# 7V_Buck_For_LDOs.net
KiCad netlist of a schematic drawn in Altium Designer
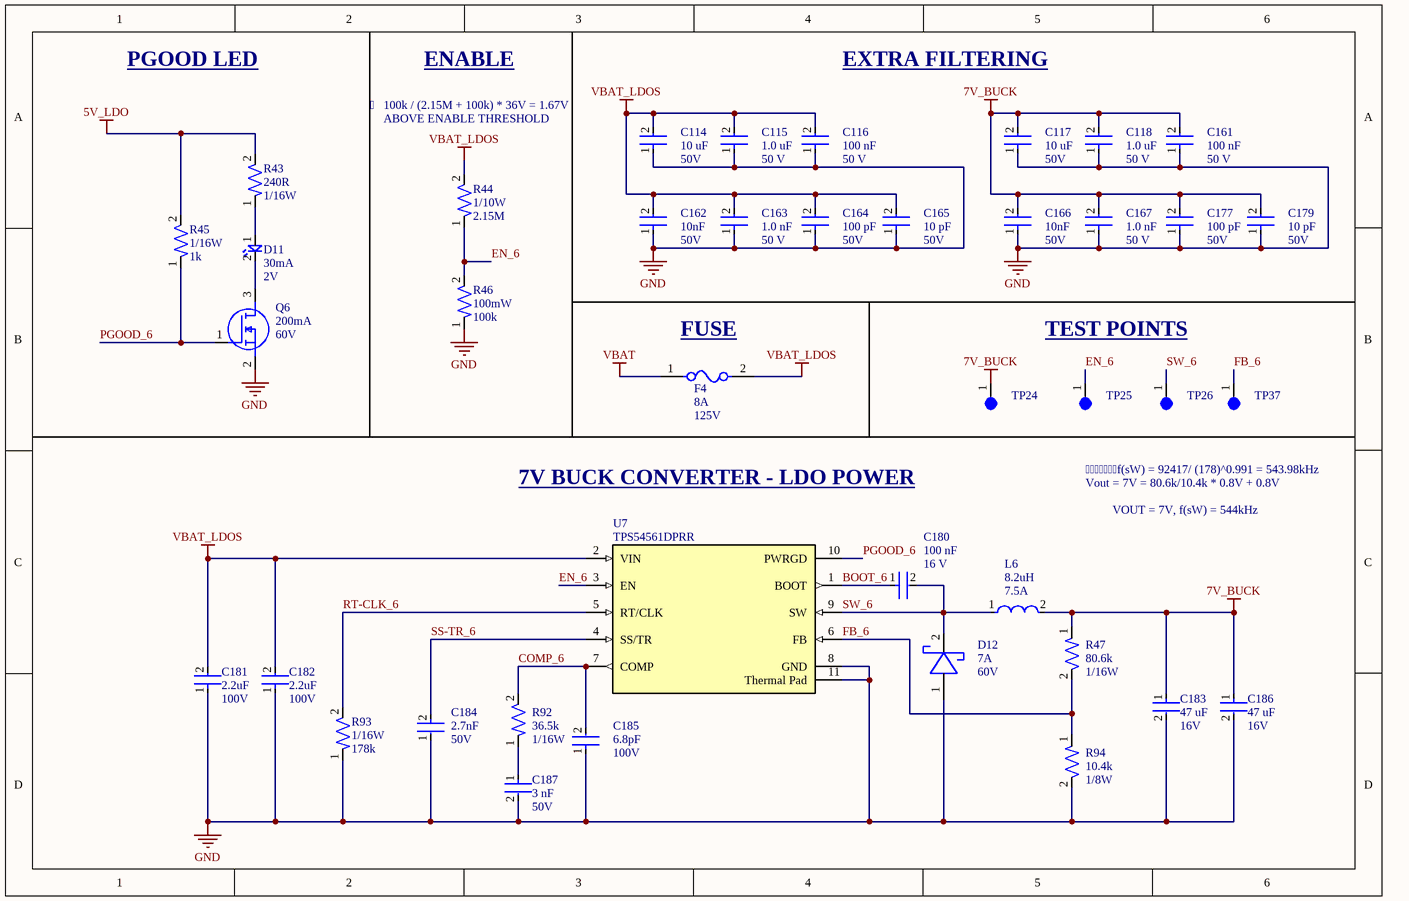
[diagram p0: 7V_Buck_For_LDOs.SchDoc]

(export (version "E")
  (design (tool "Eeschema 10.0.6"))
  (components
    (comp (ref "C114")
      (value "CL32B106KBJNNNE")
      (footprint "CAP-1210")
      (description "CAP CER 10UF 50V X7R 1210")
      (fields (field (name "VOLTAGE") "50V") (field (name "CAPACITANCE") "10 uF"))
      (libsource (lib "JLC_25") (part "CAP-10U-0002"))
    )
    (comp (ref "C115")
      (value "CC0805KKX7R9BB105")
      (footprint "CAP-0805")
      (description "CAP CER 1UF 50V X7R 0805")
      (fields (field (name "VOLTAGE") "50 V") (field (name "CAPACITANCE") "1.0 uF"))
      (libsource (lib "JLC_25") (part "CAP-1U-0001"))
    )
    (comp (ref "C116")
      (value "CC0805KRX7R9BB104")
      (footprint "CAP-0805")
      (description "CAP CER 0.1UF 50V X7R 0805")
      (fields (field (name "VOLTAGE RATING") "50 V") (field (name "CAPACITANCE") "100 nF"))
      (libsource (lib "JLC_25") (part "CAP-0.1U-0002"))
    )
    (comp (ref "C117")
      (value "CL32B106KBJNNNE")
      (footprint "CAP-1210")
      (description "CAP CER 10UF 50V X7R 1210")
      (fields (field (name "VOLTAGE") "50V") (field (name "CAPACITANCE") "10 uF"))
      (libsource (lib "JLC_25") (part "CAP-10U-0002"))
    )
    (comp (ref "C118")
      (value "CC0805KKX7R9BB105")
      (footprint "CAP-0805")
      (description "CAP CER 1UF 50V X7R 0805")
      (fields (field (name "VOLTAGE") "50 V") (field (name "CAPACITANCE") "1.0 uF"))
      (libsource (lib "JLC_25") (part "CAP-1U-0001"))
    )
    (comp (ref "C161")
      (value "CC0805KRX7R9BB104")
      (footprint "CAP-0805")
      (description "CAP CER 0.1UF 50V X7R 0805")
      (fields (field (name "VOLTAGE RATING") "50 V") (field (name "CAPACITANCE") "100 nF"))
      (libsource (lib "JLC_25") (part "CAP-0.1U-0002"))
    )
    (comp (ref "C162")
      (value "GRM2195C1H103JA01D")
      (footprint "CAP-0805")
      (description "CAP CER 10000PF 50V C0G/NP0 0805")
      (fields (field (name "VOLTAGE") "50V") (field (name "CAPACITANCE") "10nF"))
      (libsource (lib "JLC_25") (part "CAP-10N-0001"))
    )
    (comp (ref "C163")
      (value "CC0402KRX7R9BB102")
      (footprint "CAP-0402")
      (description "CAP CER 1000PF 50V X7R 0402")
      (fields (field (name "VOLTAGE") "50 V") (field (name "CAPACITANCE") "1.0 nF"))
      (libsource (lib "JLC_25") (part "CAP-1N-0001"))
    )
    (comp (ref "C164")
      (value "CC0402JRNPO9BN101")
      (footprint "CAP-0402")
      (description "CAP CER 100PF 50V C0G/NPO 0402")
      (fields (field (name "CAPACITANCE") "100 pF") (field (name "VOLTAGE") "50V"))
      (libsource (lib "JLC_25") (part "CAP-100P-0001"))
    )
    (comp (ref "C165")
      (value "CC0402JRNPO9BN100")
      (footprint "CAP-0402")
      (description "CAP CER 10PF 50V C0G/NPO 0402")
      (fields (field (name "CAPACITANCE") "10 pF") (field (name "VOLTAGE") "50V"))
      (libsource (lib "JLC_25") (part "CAP-10P-0001"))
    )
    (comp (ref "C166")
      (value "GRM2195C1H103JA01D")
      (footprint "CAP-0805")
      (description "CAP CER 10000PF 50V C0G/NP0 0805")
      (fields (field (name "VOLTAGE") "50V") (field (name "CAPACITANCE") "10nF"))
      (libsource (lib "JLC_25") (part "CAP-10N-0001"))
    )
    (comp (ref "C167")
      (value "CC0402KRX7R9BB102")
      (footprint "CAP-0402")
      (description "CAP CER 1000PF 50V X7R 0402")
      (fields (field (name "VOLTAGE") "50 V") (field (name "CAPACITANCE") "1.0 nF"))
      (libsource (lib "JLC_25") (part "CAP-1N-0001"))
    )
    (comp (ref "C177")
      (value "CC0402JRNPO9BN101")
      (footprint "CAP-0402")
      (description "CAP CER 100PF 50V C0G/NPO 0402")
      (fields (field (name "CAPACITANCE") "100 pF") (field (name "VOLTAGE") "50V"))
      (libsource (lib "JLC_25") (part "CAP-100P-0001"))
    )
    (comp (ref "C179")
      (value "CC0402JRNPO9BN100")
      (footprint "CAP-0402")
      (description "CAP CER 10PF 50V C0G/NPO 0402")
      (fields (field (name "CAPACITANCE") "10 pF") (field (name "VOLTAGE") "50V"))
      (libsource (lib "JLC_25") (part "CAP-10P-0001"))
    )
    (comp (ref "C180")
      (value "CC0402KRX7R7BB104")
      (footprint "CAP-0402")
      (description "CAP CER 0.1UF 16V X7R 0402")
      (fields (field (name "VOLTAGE RATING") "16 V") (field (name "CAPACITANCE") "100 nF"))
      (libsource (lib "JLC_25") (part "CAP-0.1U-0001"))
    )
    (comp (ref "C181")
      (value "CC1206KKX7R0BB225")
      (footprint "CAP-1206")
      (description "CAP CER 2.2UF 100V X7R 1206")
      (fields (field (name "CAPACITANCE") "2.2uF") (field (name "VOLTAGE") "100V"))
      (libsource (lib "JLC_25") (part "CAP-2.2U-0001"))
    )
    (comp (ref "C182")
      (value "CC1206KKX7R0BB225")
      (footprint "CAP-1206")
      (description "CAP CER 2.2UF 100V X7R 1206")
      (fields (field (name "CAPACITANCE") "2.2uF") (field (name "VOLTAGE") "100V"))
      (libsource (lib "JLC_25") (part "CAP-2.2U-0001"))
    )
    (comp (ref "C183")
      (value "GRM32ER61C476KE15L")
      (footprint "CAP-1210")
      (description "CAP CER 47UF 16V X5R 1210")
      (fields (field (name "CAPACITANCE") "47 uF") (field (name "VOLTAGE") "16V"))
      (libsource (lib "JLC_25") (part "CAP-47U-0002"))
    )
    (comp (ref "C184")
      (value "GRM2165C1H272JA01D")
      (footprint "CAP-0805")
      (description "CAP CER 2700PF 50V C0G/NP0 0805")
      (fields (field (name "VOLTAGE") "50V") (field (name "CAPACITANCE") "2.7nF"))
      (libsource (lib "JLC_25") (part "CAP-2.7N-0001"))
    )
    (comp (ref "C185")
      (value "CC0603CRNPO0BN6R8")
      (footprint "CAP-0603")
      (description "CAP CER 6.8PF 100V C0G/NPO 0603")
      (fields (field (name "VOLTAGE") "100V") (field (name "CAPACITANCE") "6.8pF"))
      (libsource (lib "JLC_25") (part "CAP-6.8P-0001"))
    )
    (comp (ref "C186")
      (value "GRM32ER61C476KE15L")
      (footprint "CAP-1210")
      (description "CAP CER 47UF 16V X5R 1210")
      (fields (field (name "CAPACITANCE") "47 uF") (field (name "VOLTAGE") "16V"))
      (libsource (lib "JLC_25") (part "CAP-47U-0002"))
    )
    (comp (ref "C187")
      (value "GRM1885C1H302JA01D")
      (footprint "CAP-0603")
      (description "3000 pF ±5% 50V Ceramic Capacitor C0G, NP0 0603 (1608 Metric)")
      (fields (field (name "VOLTAGE") "50V") (field (name "CAPACITANCE") "3 nF"))
      (libsource (lib "JLC_25") (part "CAP-3N-0001"))
    )
    (comp (ref "D11")
      (value "BL-HKC36G-AV-TRB")
      (footprint "LED-0603")
      (description "LED YELLOW CLEAR 0603 SMD")
      (fields (field (name "FORWARD CURRENT") "30mA") (field (name "FORWARD VOLTAGE") "2V"))
      (libsource (lib "JLC_25") (part "LED-0001"))
    )
    (comp (ref "D12")
      (value "PDS760-13")
      (footprint "DO-POWERDI5")
      (description "DIODE SCHOTTKY 60V 7A POWERDI5")
      (fields (field (name "FORWARD CURRENT") "7A") (field (name "REVERSE VOLTAGE (DC)") "60V"))
      (libsource (lib "JLC_25") (part "DIO-SCHOTTKY-0001"))
    )
    (comp (ref "F4")
      (value "01550900M")
      (footprint "FUSE-0001")
      (description "FUSE BLOK CARTRIDGE 125V 10A SMD")
      (fields (field (name "FUSE CURRENT") "8A") (field (name "VOLTAGE RATING") "125V"))
      (libsource (lib "JLC_25") (part "FUSE-0001"))
    )
    (comp (ref "L6")
      (value "IHLP2525CZER8R2M01")
      (footprint "IND25X25CZ")
      (description "8.2 µH Shielded Molded Inductor 4 A 68mOhm Max Nonstandard")
      (fields (field (name "INDUCTANCE") "8.2uH") (field (name "CURRENT RATING") "7.5A"))
      (libsource (lib "JLC_25") (part "IND-8.2U-0001"))
    )
    (comp (ref "Q6")
      (value "T2N7002AK,LM")
      (footprint "IC-SOT23-3")
      (description "MOSFET N-CH 60V 200MA SOT23")
      (fields (field (name "CONTINUOUS CURRENT") "200mA") (field (name "VOLTAGE") "60V"))
      (libsource (lib "JLC_25") (part "NMOS-200MA-0001"))
    )
    (comp (ref "R43")
      (value "RC0402FR-07240RL")
      (footprint "RES-0402")
      (description "240R 0.063W 1% 0402 (1005 Metric)  SMD")
      (fields
        (field (name "TOLERANCE") "1%")
        (field (name "RESISTANCE") "240R")
        (field (name "POWER") "1/16W")
      )
      (libsource (lib "JLC_25") (part "RES-240-0001"))
    )
    (comp (ref "R44")
      (value "RC0603FR-072M15L")
      (footprint "RES-0603")
      (description "RES SMD 2.15M OHM 1% 1/10W 0603")
      (fields
        (field (name "TOLERANCE") "1%")
        (field (name "POWER") "1/10W")
        (field (name "RESISTANCE") "2.15M")
      )
      (libsource (lib "JLC_25") (part "RES-2.15M-0001"))
    )
    (comp (ref "R45")
      (value "RC0402FR-071KL")
      (footprint "RES-0402")
      (description "RES 1K OHM 1% 1/16W 0402")
      (fields (field (name "TOLERANCE") "1%") (field (name "POWER") "1/16W") (field (name "RESISTANCE") "1k"))
      (libsource (lib "JLC_25") (part "RES-1k-0001"))
    )
    (comp (ref "R46")
      (value "RC0603FR-07100KL")
      (footprint "RES-0603")
      (description "RES SMD 100K OHM 1% 1/10W 0603")
      (fields
        (field (name "TOLERANCE") "1%")
        (field (name "POWER") "100mW")
        (field (name "RESISTANCE") "100k")
      )
      (libsource (lib "JLC_25") (part "RES-100k-0001"))
    )
    (comp (ref "R47")
      (value "RC0402FR-0780K6L")
      (footprint "RES-0402")
      (description "80.6 kOhms ±1% 0.063W, 1/16W Chip Resistor 0402 (1005 Metric) Moisture Resistant Thick Film")
      (fields
        (field (name "TOLERANCE") "1%")
        (field (name "RESISTANCE") "80.6k")
        (field (name "POWER") "1/16W")
      )
      (libsource (lib "JLC_25") (part "RES-80.6k-0001"))
    )
    (comp (ref "R92")
      (value "RC0402FR-0736K5L")
      (footprint "RES-0402")
      (description "36.5 kOhms ±1% 0.063W, 1/16W Chip Resistor 0402 (1005 Metric) Moisture Resistant Thick Film")
      (fields (field (name "POWER") "1/16W") (field (name "RESISTANCE") "36.5k"))
      (libsource (lib "JLC_25") (part "RES-36.5k-0001"))
    )
    (comp (ref "R93")
      (value "RTT021783FTH")
      (footprint "RES-0402")
      (description "62.5mW Thick Film Resistors 50V ±100ppm/℃ ±1% 178kΩ 0402 Chip Resistor - Surface Mount ROHS")
      (fields
        (field (name "TOLERANCE") "1%")
        (field (name "POWER") "1/16W")
        (field (name "RESISTANCE") "178k")
      )
      (libsource (lib "JLC_25") (part "RES-178k-0001_1"))
    )
    (comp (ref "R94")
      (value "RT0805BRD0710K4L")
      (footprint "RES-0805")
      (description "10.4 kOhms ±0.1% 0.125W, 1/8W Chip Resistor 0805 (2012 Metric) Thin Film")
      (fields
        (field (name "TOLERANCE") "1%")
        (field (name "POWER") "1/8W")
        (field (name "RESISTANCE") "10.4k")
      )
      (libsource (lib "JLC_25") (part "RES-10.4k-0001"))
    )
    (comp (ref "TP24")
      (value "5003")
      (footprint "TEST-POINT-0001")
      (description "Oranange PC Test Point, Miniature Phoisphor Bronze Silver Plating Through Hole Mounting Type")
      (libsource (lib "*") (part "TEST-POINT-0001"))
    )
    (comp (ref "TP25")
      (value "5003")
      (footprint "TEST-POINT-0001")
      (description "Oranange PC Test Point, Miniature Phoisphor Bronze Silver Plating Through Hole Mounting Type")
      (libsource (lib "*") (part "TEST-POINT-0001"))
    )
    (comp (ref "TP26")
      (value "5003")
      (footprint "TEST-POINT-0001")
      (description "Oranange PC Test Point, Miniature Phoisphor Bronze Silver Plating Through Hole Mounting Type")
      (libsource (lib "*") (part "TEST-POINT-0001"))
    )
    (comp (ref "TP37")
      (value "5003")
      (footprint "TEST-POINT-0001")
      (description "Oranange PC Test Point, Miniature Phoisphor Bronze Silver Plating Through Hole Mounting Type")
      (libsource (lib "*") (part "TEST-POINT-0001"))
    )
    (comp (ref "U7")
      (value "TPS54561DPRR")
      (footprint "IC-10WSON")
      (description "IC REG BUCK ADJ 5A 10WSON")
      (libsource (lib "JLC_25") (part "IC-BUCK-0001"))
    )
  )
  (nets
    (net (code "1") (name "/BOOT_6") (class "Default")
      (node (ref "C180") (pin "1") (pinfunction "1_1") (pintype "passive"))
      (node (ref "U7") (pin "1") (pinfunction "BOOT_1") (pintype "output"))
    )
    (net (code "2") (name "/COMP_6") (class "Default")
      (node (ref "C185") (pin "2") (pinfunction "2_2") (pintype "passive"))
      (node (ref "R92") (pin "2") (pinfunction "2_2") (pintype "passive"))
      (node (ref "U7") (pin "7") (pinfunction "COMP_7") (pintype "output"))
    )
    (net (code "3") (name "/EN_6") (class "Default")
      (node (ref "R44") (pin "1") (pinfunction "1_1") (pintype "passive"))
      (node (ref "R46") (pin "2") (pinfunction "2_2") (pintype "passive"))
      (node (ref "TP25") (pin "1") (pinfunction "0_1") (pintype "passive"))
      (node (ref "U7") (pin "3") (pinfunction "EN_3") (pintype "input"))
    )
    (net (code "4") (name "/FB_6") (class "Default")
      (node (ref "R47") (pin "2") (pinfunction "2_2") (pintype "passive"))
      (node (ref "R94") (pin "1") (pinfunction "1_1") (pintype "passive"))
      (node (ref "TP37") (pin "1") (pinfunction "0_1") (pintype "passive"))
      (node (ref "U7") (pin "6") (pinfunction "FB_6") (pintype "input"))
    )
    (net (code "5") (name "/PGOOD_6") (class "Default")
      (node (ref "Q6") (pin "1") (pinfunction "G_1") (pintype "passive"))
      (node (ref "R45") (pin "1") (pinfunction "1_1") (pintype "passive"))
      (node (ref "U7") (pin "10") (pinfunction "PWRGD_10") (pintype "open_collector"))
    )
    (net (code "6") (name "/RT-CLK_6") (class "Default")
      (node (ref "R93") (pin "2") (pinfunction "2_2") (pintype "passive"))
      (node (ref "U7") (pin "5") (pinfunction "RT/CLK_5") (pintype "input"))
    )
    (net (code "7") (name "/SS-TR_6") (class "Default")
      (node (ref "C184") (pin "2") (pinfunction "2_2") (pintype "passive"))
      (node (ref "U7") (pin "4") (pinfunction "SS/TR_4") (pintype "input"))
    )
    (net (code "8") (name "/SW_6") (class "Default")
      (node (ref "C180") (pin "2") (pinfunction "2_2") (pintype "passive"))
      (node (ref "D12") (pin "2") (pinfunction "ANODE_2") (pintype "passive"))
      (node (ref "L6") (pin "1") (pinfunction "1_1") (pintype "passive"))
      (node (ref "TP26") (pin "1") (pinfunction "0_1") (pintype "passive"))
      (node (ref "U7") (pin "9") (pinfunction "SW_9") (pintype "input"))
    )
    (net (code "9") (name "5V_LDO") (class "Default")
      (node (ref "R43") (pin "2") (pinfunction "2_2") (pintype "passive"))
      (node (ref "R45") (pin "2") (pinfunction "2_2") (pintype "passive"))
    )
    (net (code "10") (name "7V_BUCK") (class "Default")
      (node (ref "C117") (pin "2") (pinfunction "2_2") (pintype "passive"))
      (node (ref "C118") (pin "2") (pinfunction "2_2") (pintype "passive"))
      (node (ref "C161") (pin "2") (pinfunction "2_2") (pintype "passive"))
      (node (ref "C166") (pin "2") (pinfunction "2_2") (pintype "passive"))
      (node (ref "C167") (pin "2") (pinfunction "2_2") (pintype "passive"))
      (node (ref "C177") (pin "2") (pinfunction "2_2") (pintype "passive"))
      (node (ref "C179") (pin "2") (pinfunction "2_2") (pintype "passive"))
      (node (ref "C183") (pin "1") (pinfunction "1_1") (pintype "passive"))
      (node (ref "C186") (pin "1") (pinfunction "1_1") (pintype "passive"))
      (node (ref "L6") (pin "2") (pinfunction "2_2") (pintype "passive"))
      (node (ref "R47") (pin "1") (pinfunction "1_1") (pintype "passive"))
      (node (ref "TP24") (pin "1") (pinfunction "0_1") (pintype "passive"))
    )
    (net (code "11") (name "GND") (class "Default")
      (node (ref "C114") (pin "1") (pinfunction "1_1") (pintype "passive"))
      (node (ref "C115") (pin "1") (pinfunction "1_1") (pintype "passive"))
      (node (ref "C116") (pin "1") (pinfunction "1_1") (pintype "passive"))
      (node (ref "C117") (pin "1") (pinfunction "1_1") (pintype "passive"))
      (node (ref "C118") (pin "1") (pinfunction "1_1") (pintype "passive"))
      (node (ref "C161") (pin "1") (pinfunction "1_1") (pintype "passive"))
      (node (ref "C162") (pin "1") (pinfunction "1_1") (pintype "passive"))
      (node (ref "C163") (pin "1") (pinfunction "1_1") (pintype "passive"))
      (node (ref "C164") (pin "1") (pinfunction "1_1") (pintype "passive"))
      (node (ref "C165") (pin "1") (pinfunction "1_1") (pintype "passive"))
      (node (ref "C166") (pin "1") (pinfunction "1_1") (pintype "passive"))
      (node (ref "C167") (pin "1") (pinfunction "1_1") (pintype "passive"))
      (node (ref "C177") (pin "1") (pinfunction "1_1") (pintype "passive"))
      (node (ref "C179") (pin "1") (pinfunction "1_1") (pintype "passive"))
      (node (ref "C181") (pin "1") (pinfunction "1_1") (pintype "passive"))
      (node (ref "C182") (pin "1") (pinfunction "1_1") (pintype "passive"))
      (node (ref "C183") (pin "2") (pinfunction "2_2") (pintype "passive"))
      (node (ref "C184") (pin "1") (pinfunction "1_1") (pintype "passive"))
      (node (ref "C185") (pin "1") (pinfunction "1_1") (pintype "passive"))
      (node (ref "C186") (pin "2") (pinfunction "2_2") (pintype "passive"))
      (node (ref "C187") (pin "2") (pinfunction "2_2") (pintype "passive"))
      (node (ref "D12") (pin "1") (pinfunction "CATHODE_1") (pintype "passive"))
      (node (ref "Q6") (pin "2") (pinfunction "S_2") (pintype "passive"))
      (node (ref "R46") (pin "1") (pinfunction "1_1") (pintype "passive"))
      (node (ref "R93") (pin "1") (pinfunction "1_1") (pintype "passive"))
      (node (ref "R94") (pin "2") (pinfunction "2_2") (pintype "passive"))
      (node (ref "U7") (pin "11") (pinfunction "Thermal_Pad_11") (pintype "power_in"))
      (node (ref "U7") (pin "8") (pinfunction "GND_8") (pintype "power_in"))
    )
    (net (code "12") (name "Net-(C187-Pad1)") (class "Default")
      (node (ref "C187") (pin "1") (pinfunction "1_1") (pintype "passive"))
      (node (ref "R92") (pin "1") (pinfunction "1_1") (pintype "passive"))
    )
    (net (code "13") (name "Net-(D11-Pad1)") (class "Default")
      (node (ref "D11") (pin "1") (pinfunction "1_1") (pintype "passive"))
      (node (ref "R43") (pin "1") (pinfunction "1_1") (pintype "passive"))
    )
    (net (code "14") (name "Net-(Q6-D)") (class "Default")
      (node (ref "D11") (pin "2") (pinfunction "2_2") (pintype "passive"))
      (node (ref "Q6") (pin "3") (pinfunction "D_3") (pintype "passive"))
    )
    (net (code "15") (name "VBAT") (class "Default")
      (node (ref "F4") (pin "1") (pinfunction "1_1") (pintype "passive"))
    )
    (net (code "16") (name "VBAT_LDOS") (class "Default")
      (node (ref "C114") (pin "2") (pinfunction "2_2") (pintype "passive"))
      (node (ref "C115") (pin "2") (pinfunction "2_2") (pintype "passive"))
      (node (ref "C116") (pin "2") (pinfunction "2_2") (pintype "passive"))
      (node (ref "C162") (pin "2") (pinfunction "2_2") (pintype "passive"))
      (node (ref "C163") (pin "2") (pinfunction "2_2") (pintype "passive"))
      (node (ref "C164") (pin "2") (pinfunction "2_2") (pintype "passive"))
      (node (ref "C165") (pin "2") (pinfunction "2_2") (pintype "passive"))
      (node (ref "C181") (pin "2") (pinfunction "2_2") (pintype "passive"))
      (node (ref "C182") (pin "2") (pinfunction "2_2") (pintype "passive"))
      (node (ref "F4") (pin "2") (pinfunction "2_2") (pintype "passive"))
      (node (ref "R44") (pin "2") (pinfunction "2_2") (pintype "passive"))
      (node (ref "U7") (pin "2") (pinfunction "VIN_2") (pintype "input"))
    )
  )
)
